# Ethernet.net
KiCad netlist of a schematic drawn in Altium Designer
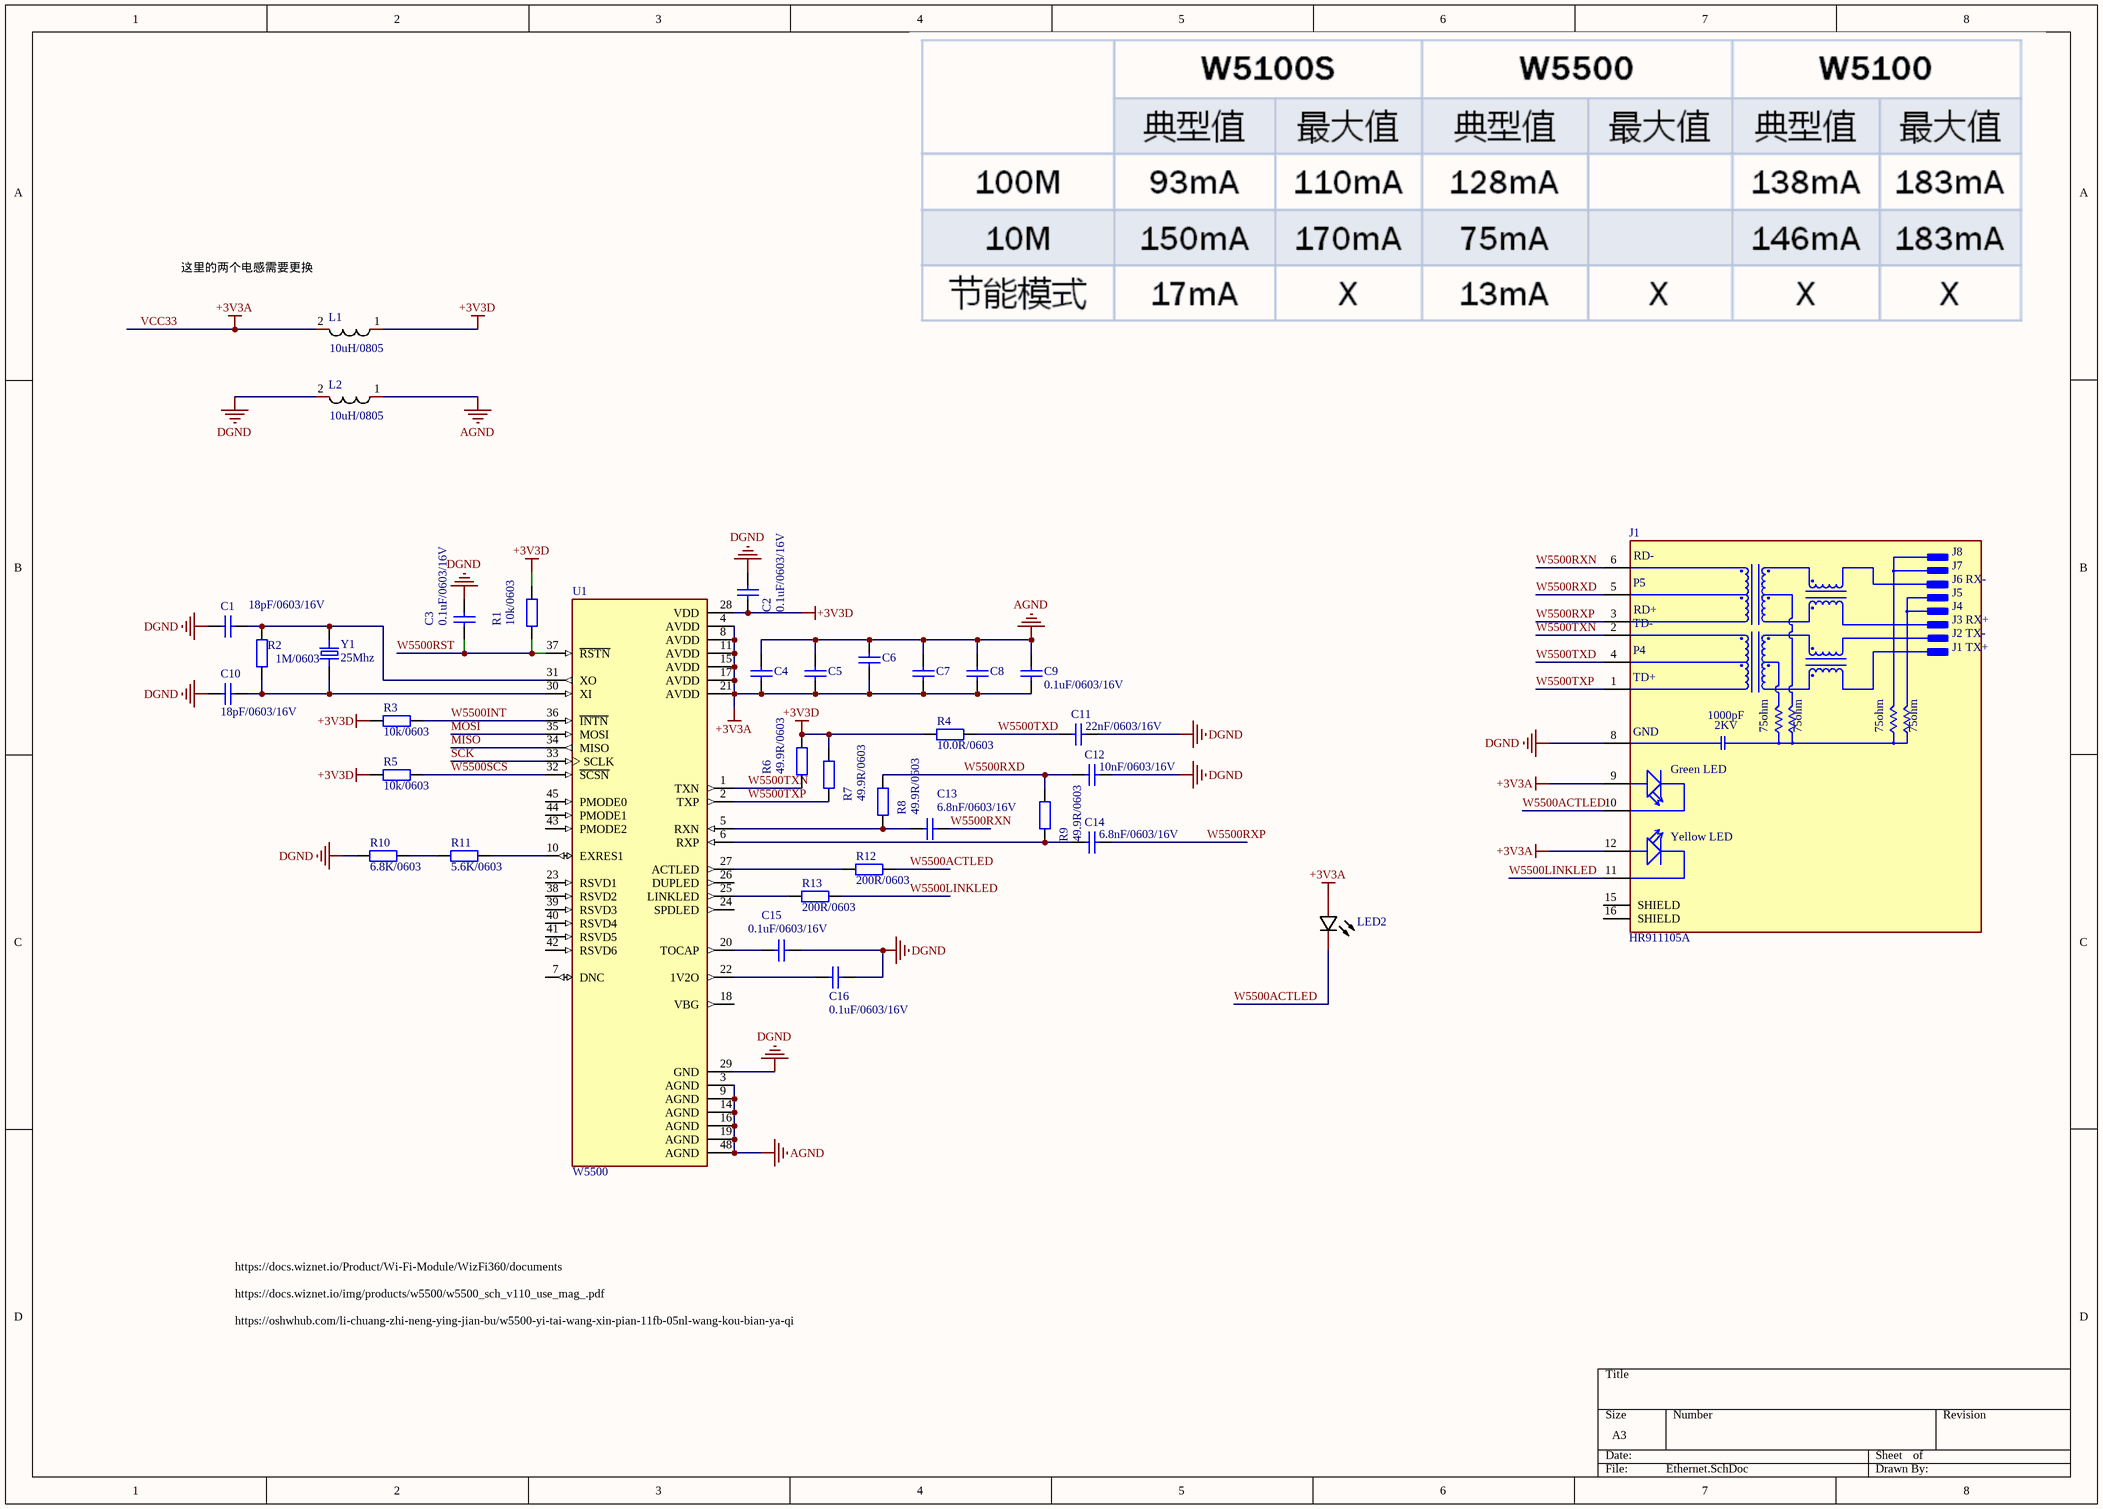
[diagram p0: Ethernet.SchDoc]

(export (version "E")
  (design (tool "Eeschema 10.0.6"))
  (components
    (comp (ref "C1")
      (value "18pF/0603/16V")
      (footprint "CAP0603")
      (description "Capacitor (Semiconductor SIM Model)")
      (fields (field (name "PUBLISHER") "Altium Limited"))
      (libsource (lib "Miscellaneous Devices") (part "Cap Semi"))
    )
    (comp (ref "C2")
      (value "0.1uF/0603/16V")
      (footprint "CAP0603")
      (description "Capacitor (Semiconductor SIM Model)")
      (fields (field (name "PUBLISHER") "Altium Limited"))
      (libsource (lib "Miscellaneous Devices") (part "Cap Semi"))
    )
    (comp (ref "C3")
      (value "0.1uF/0603/16V")
      (footprint "CAP0603")
      (description "Capacitor (Semiconductor SIM Model)")
      (fields (field (name "PUBLISHER") "Altium Limited"))
      (libsource (lib "Miscellaneous Devices") (part "Cap Semi"))
    )
    (comp (ref "C4")
      (value "0.1uF/0603/16V")
      (footprint "CAP0603")
      (description "Capacitor (Semiconductor SIM Model)")
      (fields (field (name "PUBLISHER") "Altium Limited"))
      (libsource (lib "Miscellaneous Devices") (part "Cap Semi"))
    )
    (comp (ref "C5")
      (value "0.1uF/0603/16V")
      (footprint "CAP0603")
      (description "Capacitor (Semiconductor SIM Model)")
      (fields (field (name "PUBLISHER") "Altium Limited"))
      (libsource (lib "Miscellaneous Devices") (part "Cap Semi"))
    )
    (comp (ref "C6")
      (value "0.1uF/0603/16V")
      (footprint "CAP0603")
      (description "Capacitor (Semiconductor SIM Model)")
      (fields (field (name "PUBLISHER") "Altium Limited"))
      (libsource (lib "Miscellaneous Devices") (part "Cap Semi"))
    )
    (comp (ref "C7")
      (value "0.1uF/0603/16V")
      (footprint "CAP0603")
      (description "Capacitor (Semiconductor SIM Model)")
      (fields (field (name "PUBLISHER") "Altium Limited"))
      (libsource (lib "Miscellaneous Devices") (part "Cap Semi"))
    )
    (comp (ref "C8")
      (value "0.1uF/0603/16V")
      (footprint "CAP0603")
      (description "Capacitor (Semiconductor SIM Model)")
      (fields (field (name "PUBLISHER") "Altium Limited"))
      (libsource (lib "Miscellaneous Devices") (part "Cap Semi"))
    )
    (comp (ref "C9")
      (value "0.1uF/0603/16V")
      (footprint "CAP0603")
      (description "Capacitor (Semiconductor SIM Model)")
      (fields (field (name "PUBLISHER") "Altium Limited"))
      (libsource (lib "Miscellaneous Devices") (part "Cap Semi"))
    )
    (comp (ref "C10")
      (value "18pF/0603/16V")
      (footprint "CAP0603")
      (description "Capacitor (Semiconductor SIM Model)")
      (fields (field (name "PUBLISHER") "Altium Limited"))
      (libsource (lib "Miscellaneous Devices") (part "Cap Semi"))
    )
    (comp (ref "C11")
      (value "22nF/0603/16V")
      (footprint "CAP0603")
      (description "Capacitor (Semiconductor SIM Model)")
      (fields (field (name "PUBLISHER") "Altium Limited"))
      (libsource (lib "Miscellaneous Devices") (part "Cap Semi"))
    )
    (comp (ref "C12")
      (value "10nF/0603/16V")
      (footprint "CAP0603")
      (description "Capacitor (Semiconductor SIM Model)")
      (fields (field (name "PUBLISHER") "Altium Limited"))
      (libsource (lib "Miscellaneous Devices") (part "Cap Semi"))
    )
    (comp (ref "C13")
      (value "6.8nF/0603/16V")
      (footprint "CAP0603")
      (description "Capacitor (Semiconductor SIM Model)")
      (fields (field (name "PUBLISHER") "Altium Limited"))
      (libsource (lib "Miscellaneous Devices") (part "Cap Semi"))
    )
    (comp (ref "C14")
      (value "6.8nF/0603/16V")
      (footprint "CAP0603")
      (description "Capacitor (Semiconductor SIM Model)")
      (fields (field (name "PUBLISHER") "Altium Limited"))
      (libsource (lib "Miscellaneous Devices") (part "Cap Semi"))
    )
    (comp (ref "C15")
      (value "0.1uF/0603/16V")
      (footprint "CAP0603")
      (description "Capacitor (Semiconductor SIM Model)")
      (fields (field (name "PUBLISHER") "Altium Limited"))
      (libsource (lib "Miscellaneous Devices") (part "Cap Semi"))
    )
    (comp (ref "C16")
      (value "0.1uF/0603/16V")
      (footprint "CAP0603")
      (description "Capacitor (Semiconductor SIM Model)")
      (fields (field (name "PUBLISHER") "Altium Limited"))
      (libsource (lib "Miscellaneous Devices") (part "Cap Semi"))
    )
    (comp (ref "J1")
      (value "HR911105A")
      (footprint "HANRUN_HR911105A")
      (libsource (lib "ChargingPile") (part "HR911105A"))
    )
    (comp (ref "L1")
      (value "10uH/0805")
      (footprint "RES0805")
      (libsource (lib "altium-import") (part "root_2_IND-MOLDED_"))
    )
    (comp (ref "L2")
      (value "10uH/0805")
      (footprint "RES0805")
      (libsource (lib "altium-import") (part "root_2_IND-MOLDED_"))
    )
    (comp (ref "LED2")
      (value "19-217/GHC-YR1S2/3T")
      (footprint "LED_0603_KA")
      (fields (field (name "MANUFACTURER") "EVERLIGHT"))
      (libsource (lib "altium-import") (part "root_3_19-217/GHC-YR1S2/3T_"))
    )
    (comp (ref "R1")
      (value "10k/0603")
      (footprint "R0603")
      (description "Resistor")
      (fields (field (name "PUBLISHER") "Altium Limited"))
      (libsource (lib "Miscellaneous Devices") (part "Res2"))
    )
    (comp (ref "R2")
      (value "1M/0603")
      (footprint "R0603")
      (description "Resistor")
      (fields (field (name "PUBLISHER") "Altium Limited"))
      (libsource (lib "Miscellaneous Devices") (part "Res2"))
    )
    (comp (ref "R3")
      (value "10k/0603")
      (footprint "R0603")
      (description "Resistor")
      (fields (field (name "PUBLISHER") "Altium Limited"))
      (libsource (lib "") (part "Res2_1"))
    )
    (comp (ref "R4")
      (value "10.0R/0603")
      (footprint "R0603")
      (description "Resistor")
      (fields (field (name "PUBLISHER") "Altium Limited"))
      (libsource (lib "") (part "Res2_1"))
    )
    (comp (ref "R5")
      (value "10k/0603")
      (footprint "R0603")
      (description "Resistor")
      (fields (field (name "PUBLISHER") "Altium Limited"))
      (libsource (lib "") (part "Res2_1"))
    )
    (comp (ref "R6")
      (value "49.9R/0603")
      (footprint "R0603")
      (description "Resistor")
      (fields (field (name "PUBLISHER") "Altium Limited"))
      (libsource (lib "Miscellaneous Devices") (part "Res2"))
    )
    (comp (ref "R7")
      (value "49.9R/0603")
      (footprint "R0603")
      (description "Resistor")
      (fields (field (name "PUBLISHER") "Altium Limited"))
      (libsource (lib "Miscellaneous Devices") (part "Res2"))
    )
    (comp (ref "R8")
      (value "49.9R/0603")
      (footprint "R0603")
      (description "Resistor")
      (fields (field (name "PUBLISHER") "Altium Limited"))
      (libsource (lib "Miscellaneous Devices") (part "Res2"))
    )
    (comp (ref "R9")
      (value "49.9R/0603")
      (footprint "R0603")
      (description "Resistor")
      (fields (field (name "PUBLISHER") "Altium Limited"))
      (libsource (lib "Miscellaneous Devices") (part "Res2"))
    )
    (comp (ref "R10")
      (value "6.8K/0603")
      (footprint "R0603")
      (description "Resistor")
      (fields (field (name "PUBLISHER") "Altium Limited"))
      (libsource (lib "") (part "Res2_1"))
    )
    (comp (ref "R11")
      (value "5.6K/0603")
      (footprint "R0603")
      (description "Resistor")
      (fields (field (name "PUBLISHER") "Altium Limited"))
      (libsource (lib "") (part "Res2_1"))
    )
    (comp (ref "R12")
      (value "200R/0603")
      (footprint "R0603")
      (description "Resistor")
      (fields (field (name "PUBLISHER") "Altium Limited"))
      (libsource (lib "") (part "Res2_1"))
    )
    (comp (ref "R13")
      (value "200R/0603")
      (footprint "R0603")
      (description "Resistor")
      (fields (field (name "PUBLISHER") "Altium Limited"))
      (libsource (lib "") (part "Res2_1"))
    )
    (comp (ref "U1")
      (value "W5500")
      (footprint "W5500-LQFP50P900X900X160-48N")
      (libsource (lib "ChargingPile") (part "W5500"))
    )
    (comp (ref "Y1")
      (value "25Mhz")
      (footprint "XTAL_ECS-250-20-4X-F-DN")
      (description "25 MHz ±30ppm Crystal 20pF 30 Ohms HC-49/US")
      (fields (field (name "MF") "ECS Inc.") (field (name "MP") "ECS-250-20-4X-F-DN"))
      (libsource (lib "ChargingPile") (part "25Mhz-ECS-250-20-4X-F-DN"))
    )
  )
  (nets
    (net (code "1") (name "+3V3A") (class "Default")
      (node (ref "C4") (pin "1") (pinfunction "1_1") (pintype "passive"))
      (node (ref "C5") (pin "1") (pinfunction "1_1") (pintype "passive"))
      (node (ref "C6") (pin "1") (pinfunction "1_1") (pintype "passive"))
      (node (ref "C7") (pin "1") (pinfunction "1_1") (pintype "passive"))
      (node (ref "C8") (pin "1") (pinfunction "1_1") (pintype "passive"))
      (node (ref "C9") (pin "1") (pinfunction "1_1") (pintype "passive"))
      (node (ref "J1") (pin "12") (pinfunction "YA_12") (pintype "passive"))
      (node (ref "J1") (pin "9") (pinfunction "GA_9") (pintype "passive"))
      (node (ref "L1") (pin "2") (pintype "passive"))
      (node (ref "LED2") (pin "1") (pinfunction "A_1") (pintype "passive"))
      (node (ref "U1") (pin "11") (pinfunction "AVDD_11") (pintype "power_in"))
      (node (ref "U1") (pin "15") (pinfunction "AVDD_15") (pintype "power_in"))
      (node (ref "U1") (pin "17") (pinfunction "AVDD_17") (pintype "power_in"))
      (node (ref "U1") (pin "21") (pinfunction "AVDD_21") (pintype "power_in"))
      (node (ref "U1") (pin "4") (pinfunction "AVDD_4") (pintype "power_in"))
      (node (ref "U1") (pin "8") (pinfunction "AVDD_8") (pintype "power_in"))
    )
    (net (code "2") (name "+3V3D") (class "Default")
      (node (ref "C2") (pin "2") (pinfunction "2_2") (pintype "passive"))
      (node (ref "L1") (pin "1") (pintype "passive"))
      (node (ref "R1") (pin "2") (pinfunction "2_2") (pintype "passive"))
      (node (ref "R3") (pin "2") (pinfunction "2_2") (pintype "passive"))
      (node (ref "R4") (pin "2") (pinfunction "2_2") (pintype "passive"))
      (node (ref "R5") (pin "2") (pinfunction "2_2") (pintype "passive"))
      (node (ref "R6") (pin "2") (pinfunction "2_2") (pintype "passive"))
      (node (ref "R7") (pin "2") (pinfunction "2_2") (pintype "passive"))
      (node (ref "U1") (pin "28") (pinfunction "VDD_28") (pintype "power_in"))
    )
    (net (code "3") (name "/MISO") (class "Default")
      (node (ref "U1") (pin "34") (pinfunction "MISO_34") (pintype "output"))
    )
    (net (code "4") (name "/MOSI") (class "Default")
      (node (ref "U1") (pin "35") (pinfunction "MOSI_35") (pintype "input"))
    )
    (net (code "5") (name "/SCK") (class "Default")
      (node (ref "U1") (pin "33") (pinfunction "SCLK_33") (pintype "input"))
    )
    (net (code "6") (name "/W5500ACTLED") (class "Default")
      (node (ref "J1") (pin "10") (pinfunction "GC_10") (pintype "passive"))
      (node (ref "LED2") (pin "2") (pinfunction "C_2") (pintype "passive"))
      (node (ref "R12") (pin "1") (pinfunction "1_1") (pintype "passive"))
    )
    (net (code "7") (name "/W5500INT") (class "Default")
      (node (ref "R3") (pin "1") (pinfunction "1_1") (pintype "passive"))
      (node (ref "U1") (pin "36") (pinfunction "~{INTN}_36") (pintype "input"))
    )
    (net (code "8") (name "/W5500LINKLED") (class "Default")
      (node (ref "J1") (pin "11") (pinfunction "YC_11") (pintype "passive"))
      (node (ref "R13") (pin "1") (pinfunction "1_1") (pintype "passive"))
    )
    (net (code "9") (name "/W5500RST") (class "Default")
      (node (ref "C3") (pin "1") (pinfunction "1_1") (pintype "passive"))
      (node (ref "R1") (pin "1") (pinfunction "1_1") (pintype "passive"))
      (node (ref "U1") (pin "37") (pinfunction "~{RSTN}_37") (pintype "input"))
    )
    (net (code "10") (name "/W5500RXD") (class "Default")
      (node (ref "C12") (pin "1") (pinfunction "1_1") (pintype "passive"))
      (node (ref "J1") (pin "5") (pinfunction "P5_5") (pintype "passive"))
      (node (ref "R8") (pin "2") (pinfunction "2_2") (pintype "passive"))
      (node (ref "R9") (pin "2") (pinfunction "2_2") (pintype "passive"))
    )
    (net (code "11") (name "/W5500RXN") (class "Default")
      (node (ref "C13") (pin "2") (pinfunction "2_2") (pintype "passive"))
      (node (ref "J1") (pin "6") (pinfunction "RD-_6") (pintype "passive"))
    )
    (net (code "12") (name "/W5500RXP") (class "Default")
      (node (ref "C14") (pin "2") (pinfunction "2_2") (pintype "passive"))
      (node (ref "J1") (pin "3") (pinfunction "RD+_3") (pintype "passive"))
    )
    (net (code "13") (name "/W5500SCS") (class "Default")
      (node (ref "R5") (pin "1") (pinfunction "1_1") (pintype "passive"))
      (node (ref "U1") (pin "32") (pinfunction "~{SCSN}_32") (pintype "input"))
    )
    (net (code "14") (name "/W5500TXD") (class "Default")
      (node (ref "C11") (pin "1") (pinfunction "1_1") (pintype "passive"))
      (node (ref "J1") (pin "4") (pinfunction "P4_4") (pintype "passive"))
      (node (ref "R4") (pin "1") (pinfunction "1_1") (pintype "passive"))
    )
    (net (code "15") (name "/W5500TXN") (class "Default")
      (node (ref "J1") (pin "2") (pinfunction "TD-_2") (pintype "passive"))
      (node (ref "R6") (pin "1") (pinfunction "1_1") (pintype "passive"))
      (node (ref "U1") (pin "1") (pinfunction "TXN_1") (pintype "output"))
    )
    (net (code "16") (name "/W5500TXP") (class "Default")
      (node (ref "J1") (pin "1") (pinfunction "TD+_1") (pintype "passive"))
      (node (ref "R7") (pin "1") (pinfunction "1_1") (pintype "passive"))
      (node (ref "U1") (pin "2") (pinfunction "TXP_2") (pintype "output"))
    )
    (net (code "17") (name "AGND") (class "Default")
      (node (ref "C4") (pin "2") (pinfunction "2_2") (pintype "passive"))
      (node (ref "C5") (pin "2") (pinfunction "2_2") (pintype "passive"))
      (node (ref "C6") (pin "2") (pinfunction "2_2") (pintype "passive"))
      (node (ref "C7") (pin "2") (pinfunction "2_2") (pintype "passive"))
      (node (ref "C8") (pin "2") (pinfunction "2_2") (pintype "passive"))
      (node (ref "C9") (pin "2") (pinfunction "2_2") (pintype "passive"))
      (node (ref "L2") (pin "1") (pintype "passive"))
      (node (ref "U1") (pin "14") (pinfunction "AGND_14") (pintype "power_in"))
      (node (ref "U1") (pin "16") (pinfunction "AGND_16") (pintype "power_in"))
      (node (ref "U1") (pin "19") (pinfunction "AGND_19") (pintype "power_in"))
      (node (ref "U1") (pin "3") (pinfunction "AGND_3") (pintype "power_in"))
      (node (ref "U1") (pin "48") (pinfunction "AGND_48") (pintype "power_in"))
      (node (ref "U1") (pin "9") (pinfunction "AGND_9") (pintype "power_in"))
    )
    (net (code "18") (name "DGND") (class "Default")
      (node (ref "C1") (pin "1") (pinfunction "1_1") (pintype "passive"))
      (node (ref "C10") (pin "1") (pinfunction "1_1") (pintype "passive"))
      (node (ref "C11") (pin "2") (pinfunction "2_2") (pintype "passive"))
      (node (ref "C12") (pin "2") (pinfunction "2_2") (pintype "passive"))
      (node (ref "C15") (pin "1") (pinfunction "1_1") (pintype "passive"))
      (node (ref "C16") (pin "1") (pinfunction "1_1") (pintype "passive"))
      (node (ref "C2") (pin "1") (pinfunction "1_1") (pintype "passive"))
      (node (ref "C3") (pin "2") (pinfunction "2_2") (pintype "passive"))
      (node (ref "J1") (pin "8") (pinfunction "GND_8") (pintype "power_in"))
      (node (ref "L2") (pin "2") (pintype "passive"))
      (node (ref "R10") (pin "2") (pinfunction "2_2") (pintype "passive"))
      (node (ref "U1") (pin "29") (pinfunction "GND_29") (pintype "passive"))
    )
    (net (code "19") (name "Net-(R10-Pad1)") (class "Default")
      (node (ref "R10") (pin "1") (pinfunction "1_1") (pintype "passive"))
      (node (ref "R11") (pin "2") (pinfunction "2_2") (pintype "passive"))
    )
    (net (code "20") (name "Net-(U1-1V2O)") (class "Default")
      (node (ref "C16") (pin "2") (pinfunction "2_2") (pintype "passive"))
      (node (ref "U1") (pin "22") (pinfunction "1V2O_22") (pintype "output"))
    )
    (net (code "21") (name "Net-(U1-ACTLED)") (class "Default")
      (node (ref "R12") (pin "2") (pinfunction "2_2") (pintype "passive"))
      (node (ref "U1") (pin "27") (pinfunction "ACTLED_27") (pintype "output"))
    )
    (net (code "22") (name "Net-(U1-EXRES1)") (class "Default")
      (node (ref "R11") (pin "1") (pinfunction "1_1") (pintype "passive"))
      (node (ref "U1") (pin "10") (pinfunction "EXRES1_10") (pintype "bidirectional"))
    )
    (net (code "23") (name "Net-(U1-LINKLED)") (class "Default")
      (node (ref "R13") (pin "2") (pinfunction "2_2") (pintype "passive"))
      (node (ref "U1") (pin "25") (pinfunction "LINKLED_25") (pintype "output"))
    )
    (net (code "24") (name "Net-(U1-RXN)") (class "Default")
      (node (ref "C13") (pin "1") (pinfunction "1_1") (pintype "passive"))
      (node (ref "R8") (pin "1") (pinfunction "1_1") (pintype "passive"))
      (node (ref "U1") (pin "5") (pinfunction "RXN_5") (pintype "input"))
    )
    (net (code "25") (name "Net-(U1-RXP)") (class "Default")
      (node (ref "C14") (pin "1") (pinfunction "1_1") (pintype "passive"))
      (node (ref "R9") (pin "1") (pinfunction "1_1") (pintype "passive"))
      (node (ref "U1") (pin "6") (pinfunction "RXP_6") (pintype "input"))
    )
    (net (code "26") (name "Net-(U1-TOCAP)") (class "Default")
      (node (ref "C15") (pin "2") (pinfunction "2_2") (pintype "passive"))
      (node (ref "U1") (pin "20") (pinfunction "TOCAP_20") (pintype "output"))
    )
    (net (code "27") (name "Net-(U1-XI)") (class "Default")
      (node (ref "C10") (pin "2") (pinfunction "2_2") (pintype "passive"))
      (node (ref "R2") (pin "1") (pinfunction "1_1") (pintype "passive"))
      (node (ref "U1") (pin "30") (pinfunction "XI_30") (pintype "input"))
      (node (ref "Y1") (pin "1") (pinfunction "1_1") (pintype "passive"))
    )
    (net (code "28") (name "Net-(U1-XO)") (class "Default")
      (node (ref "C1") (pin "2") (pinfunction "2_2") (pintype "passive"))
      (node (ref "R2") (pin "2") (pinfunction "2_2") (pintype "passive"))
      (node (ref "U1") (pin "31") (pinfunction "XO_31") (pintype "output"))
      (node (ref "Y1") (pin "2") (pinfunction "2_2") (pintype "passive"))
    )
    (net (code "29") (name "unconnected-(J1-SHIELD-Pad15)") (class "Default")
      (node (ref "J1") (pin "15") (pinfunction "SHIELD_15") (pintype "passive"))
    )
    (net (code "30") (name "unconnected-(J1-SHIELD-Pad16)") (class "Default")
      (node (ref "J1") (pin "16") (pinfunction "SHIELD_16") (pintype "passive"))
    )
    (net (code "31") (name "unconnected-(U1-DNC-Pad7)") (class "Default")
      (node (ref "U1") (pin "7") (pinfunction "DNC_7") (pintype "bidirectional"))
    )
    (net (code "32") (name "unconnected-(U1-DUPLED-Pad26)") (class "Default")
      (node (ref "U1") (pin "26") (pinfunction "DUPLED_26") (pintype "output"))
    )
    (net (code "33") (name "unconnected-(U1-PMODE0-Pad45)") (class "Default")
      (node (ref "U1") (pin "45") (pinfunction "PMODE0_45") (pintype "input"))
    )
    (net (code "34") (name "unconnected-(U1-PMODE1-Pad44)") (class "Default")
      (node (ref "U1") (pin "44") (pinfunction "PMODE1_44") (pintype "input"))
    )
    (net (code "35") (name "unconnected-(U1-PMODE2-Pad43)") (class "Default")
      (node (ref "U1") (pin "43") (pinfunction "PMODE2_43") (pintype "input"))
    )
    (net (code "36") (name "unconnected-(U1-RSVD1-Pad23)") (class "Default")
      (node (ref "U1") (pin "23") (pinfunction "RSVD1_23") (pintype "input"))
    )
    (net (code "37") (name "unconnected-(U1-RSVD2-Pad38)") (class "Default")
      (node (ref "U1") (pin "38") (pinfunction "RSVD2_38") (pintype "input"))
    )
    (net (code "38") (name "unconnected-(U1-RSVD3-Pad39)") (class "Default")
      (node (ref "U1") (pin "39") (pinfunction "RSVD3_39") (pintype "input"))
    )
    (net (code "39") (name "unconnected-(U1-RSVD4-Pad40)") (class "Default")
      (node (ref "U1") (pin "40") (pinfunction "RSVD4_40") (pintype "input"))
    )
    (net (code "40") (name "unconnected-(U1-RSVD5-Pad41)") (class "Default")
      (node (ref "U1") (pin "41") (pinfunction "RSVD5_41") (pintype "input"))
    )
    (net (code "41") (name "unconnected-(U1-RSVD6-Pad42)") (class "Default")
      (node (ref "U1") (pin "42") (pinfunction "RSVD6_42") (pintype "input"))
    )
    (net (code "42") (name "unconnected-(U1-SPDLED-Pad24)") (class "Default")
      (node (ref "U1") (pin "24") (pinfunction "SPDLED_24") (pintype "output"))
    )
    (net (code "43") (name "unconnected-(U1-VBG-Pad18)") (class "Default")
      (node (ref "U1") (pin "18") (pinfunction "VBG_18") (pintype "output"))
    )
  )
)
